# Bran_Download.net
KiCad netlist of a schematic drawn in Altium Designer
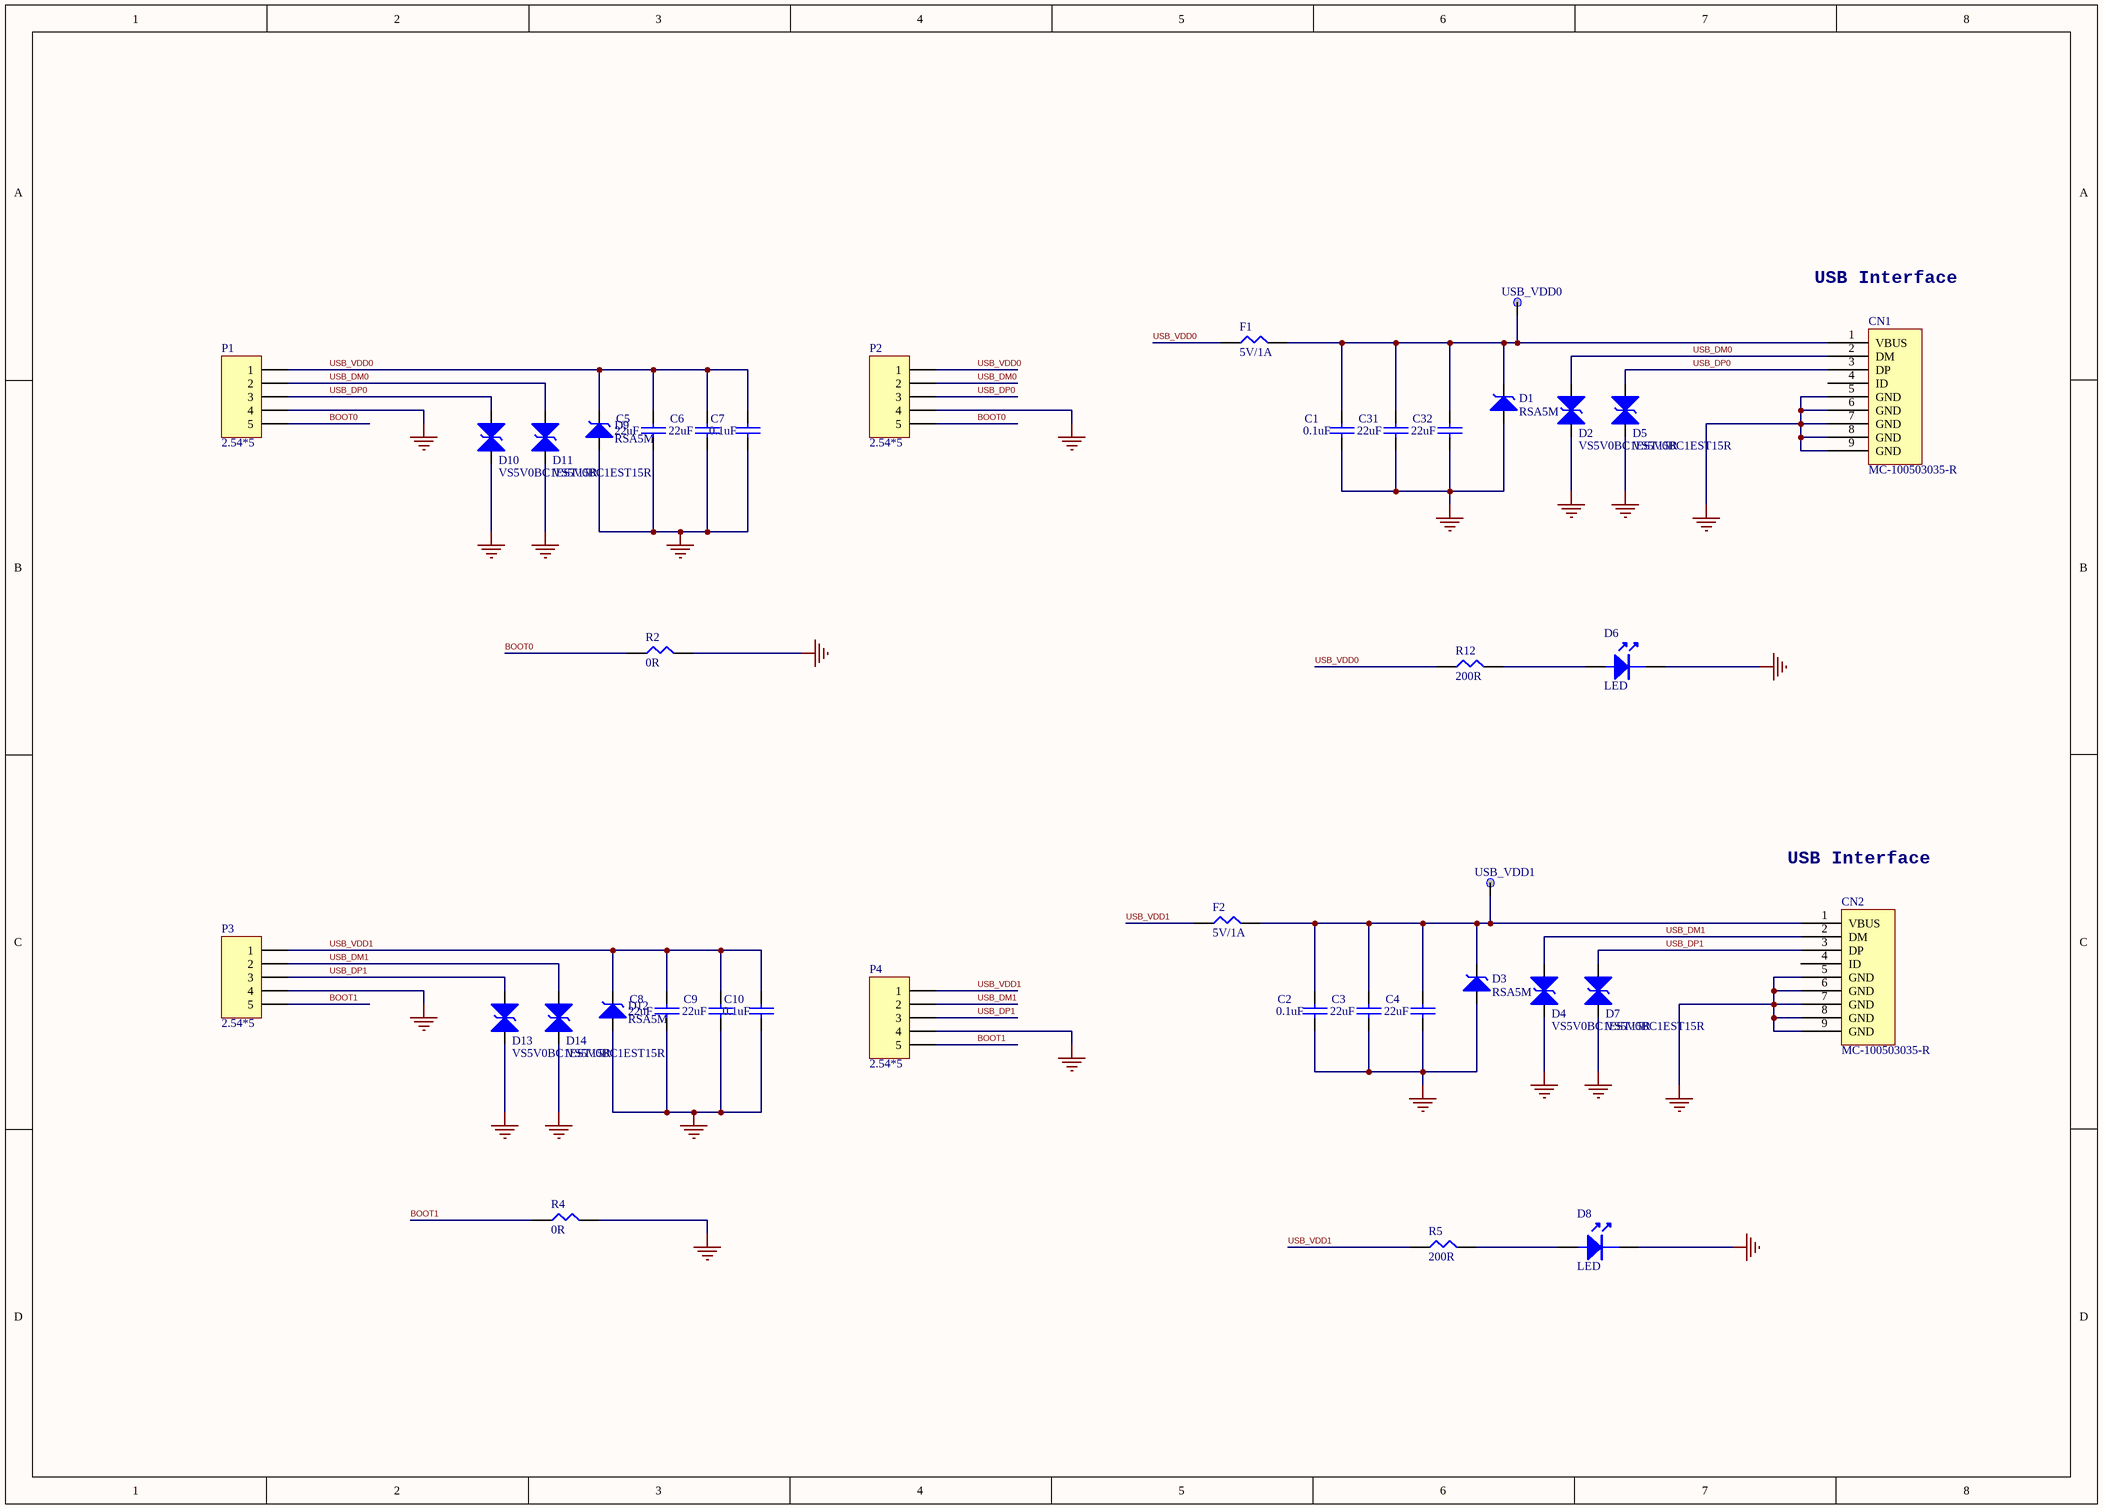
[diagram p0: Bran_Download.SchDoc]

(export (version "E")
  (design (tool "Eeschema 10.0.6"))
  (components
    (comp (ref "C1")
      (value "0.1uF")
      (footprint "0603C")
      (description "厂家：Murata，型号：GRM188R61A106KE69D")
      (libsource (lib "*") (part "CAP"))
    )
    (comp (ref "C2")
      (value "0.1uF")
      (footprint "0603C")
      (description "厂家：Murata，型号：GRM188R61A106KE69D")
      (libsource (lib "*") (part "CAP"))
    )
    (comp (ref "C3")
      (value "22uF")
      (footprint "0603C")
      (description "厂家：Murata，型号：GRM188R61A106KE69D")
      (libsource (lib "*") (part "CAP"))
    )
    (comp (ref "C4")
      (value "22uF")
      (footprint "0603C")
      (description "厂家：Murata，型号：GRM188R61A106KE69D")
      (libsource (lib "*") (part "CAP"))
    )
    (comp (ref "C5")
      (value "22uF")
      (footprint "0603C")
      (description "厂家：Murata，型号：GRM188R61A106KE69D")
      (libsource (lib "*") (part "CAP"))
    )
    (comp (ref "C6")
      (value "22uF")
      (footprint "0603C")
      (description "厂家：Murata，型号：GRM188R61A106KE69D")
      (libsource (lib "*") (part "CAP"))
    )
    (comp (ref "C7")
      (value "0.1uF")
      (footprint "0603C")
      (description "厂家：Murata，型号：GRM188R61A106KE69D")
      (libsource (lib "*") (part "CAP"))
    )
    (comp (ref "C8")
      (value "22uF")
      (footprint "0603C")
      (description "厂家：Murata，型号：GRM188R61A106KE69D")
      (libsource (lib "*") (part "CAP"))
    )
    (comp (ref "C9")
      (value "22uF")
      (footprint "0603C")
      (description "厂家：Murata，型号：GRM188R61A106KE69D")
      (libsource (lib "*") (part "CAP"))
    )
    (comp (ref "C10")
      (value "0.1uF")
      (footprint "0603C")
      (description "厂家：Murata，型号：GRM188R61A106KE69D")
      (libsource (lib "*") (part "CAP"))
    )
    (comp (ref "C31")
      (value "22uF")
      (footprint "0603C")
      (description "厂家：Murata，型号：GRM188R61A106KE69D")
      (libsource (lib "*") (part "CAP"))
    )
    (comp (ref "C32")
      (value "22uF")
      (footprint "0603C")
      (description "厂家：Murata，型号：GRM188R61A106KE69D")
      (libsource (lib "*") (part "CAP"))
    )
    (comp (ref "CN1")
      (value "MC-100503035-R")
      (footprint "MICRO-USB-乐沪")
      (libsource (lib "mic_usb_assy FPC") (part "475900001"))
    )
    (comp (ref "CN2")
      (value "MC-100503035-R")
      (footprint "MICRO-USB-乐沪")
      (libsource (lib "mic_usb_assy FPC") (part "475900001"))
    )
    (comp (ref "D1")
      (value "RSA5M")
      (footprint "PMDU")
      (description "厂家：ROHM，型号：VMNZC6.8CST2RA")
      (libsource (lib "CCS801 VOC") (part "ESD_1"))
    )
    (comp (ref "D2")
      (value "VS5V0BC1EST15R")
      (footprint "ESD_0402")
      (description "厂家：ROHM，型号：VMNZC6.8CST2RA")
      (libsource (lib "Amber") (part "ESD_1"))
    )
    (comp (ref "D3")
      (value "RSA5M")
      (footprint "PMDU")
      (description "厂家：ROHM，型号：VMNZC6.8CST2RA")
      (libsource (lib "CCS801 VOC") (part "ESD_1"))
    )
    (comp (ref "D4")
      (value "VS5V0BC1EST15R")
      (footprint "ESD_0402")
      (description "厂家：ROHM，型号：VMNZC6.8CST2RA")
      (libsource (lib "Amber") (part "ESD_1"))
    )
    (comp (ref "D5")
      (value "VS5V0BC1EST15R")
      (footprint "ESD_0402")
      (description "厂家：ROHM，型号：VMNZC6.8CST2RA")
      (libsource (lib "Amber") (part "ESD_1"))
    )
    (comp (ref "D6")
      (value "LED")
      (footprint "0402LED")
      (description "厂家：ROHM，型号：SCMP13WBC8W1**")
      (libsource (lib "Schlib1") (part "LED"))
    )
    (comp (ref "D7")
      (value "VS5V0BC1EST15R")
      (footprint "ESD_0402")
      (description "厂家：ROHM，型号：VMNZC6.8CST2RA")
      (libsource (lib "Amber") (part "ESD_1"))
    )
    (comp (ref "D8")
      (value "LED")
      (footprint "0402LED")
      (description "厂家：ROHM，型号：SCMP13WBC8W1**")
      (libsource (lib "Schlib1") (part "LED"))
    )
    (comp (ref "D9")
      (value "RSA5M")
      (footprint "PMDU")
      (description "厂家：ROHM，型号：VMNZC6.8CST2RA")
      (libsource (lib "CCS801 VOC") (part "ESD_1"))
    )
    (comp (ref "D10")
      (value "VS5V0BC1EST15R")
      (footprint "ESD_0402")
      (description "厂家：ROHM，型号：VMNZC6.8CST2RA")
      (libsource (lib "Amber") (part "ESD_1"))
    )
    (comp (ref "D11")
      (value "VS5V0BC1EST15R")
      (footprint "ESD_0402")
      (description "厂家：ROHM，型号：VMNZC6.8CST2RA")
      (libsource (lib "Amber") (part "ESD_1"))
    )
    (comp (ref "D12")
      (value "RSA5M")
      (footprint "PMDU")
      (description "厂家：ROHM，型号：VMNZC6.8CST2RA")
      (libsource (lib "CCS801 VOC") (part "ESD_1"))
    )
    (comp (ref "D13")
      (value "VS5V0BC1EST15R")
      (footprint "ESD_0402")
      (description "厂家：ROHM，型号：VMNZC6.8CST2RA")
      (libsource (lib "Amber") (part "ESD_1"))
    )
    (comp (ref "D14")
      (value "VS5V0BC1EST15R")
      (footprint "ESD_0402")
      (description "厂家：ROHM，型号：VMNZC6.8CST2RA")
      (libsource (lib "Amber") (part "ESD_1"))
    )
    (comp (ref "F1")
      (value "5V/1A")
      (footprint "0603R")
      (description "厂家：Yageo，型号：RC0402FR-07100KL")
      (libsource (lib "Schlib1") (part "RES"))
    )
    (comp (ref "F2")
      (value "5V/1A")
      (footprint "0603R")
      (description "厂家：Yageo，型号：RC0402FR-07100KL")
      (libsource (lib "Schlib1") (part "RES"))
    )
    (comp (ref "P1")
      (value "2.54*5")
      (footprint "HDR1X5")
      (description "Header, 5-Pin")
      (fields (field (name "PUBLISHER") "Altium Limited"))
      (libsource (lib "Miscellaneous Connectors") (part "Header 5"))
    )
    (comp (ref "P2")
      (value "2.54*5")
      (footprint "HDR1X5")
      (description "Header, 5-Pin")
      (fields (field (name "PUBLISHER") "Altium Limited"))
      (libsource (lib "Miscellaneous Connectors") (part "Header 5"))
    )
    (comp (ref "P3")
      (value "2.54*5")
      (footprint "HDR1X5")
      (description "Header, 5-Pin")
      (fields (field (name "PUBLISHER") "Altium Limited"))
      (libsource (lib "Miscellaneous Connectors") (part "Header 5"))
    )
    (comp (ref "P4")
      (value "2.54*5")
      (footprint "HDR1X5")
      (description "Header, 5-Pin")
      (fields (field (name "PUBLISHER") "Altium Limited"))
      (libsource (lib "Miscellaneous Connectors") (part "Header 5"))
    )
    (comp (ref "R2")
      (value "0R")
      (footprint "0603R")
      (description "厂家：Yageo，型号：RC0402FR-07100KL")
      (libsource (lib "Schlib1") (part "RES"))
    )
    (comp (ref "R4")
      (value "0R")
      (footprint "0603R")
      (description "厂家：Yageo，型号：RC0402FR-07100KL")
      (libsource (lib "Schlib1") (part "RES"))
    )
    (comp (ref "R5")
      (value "200R")
      (footprint "0603R")
      (description "厂家：Yageo，型号：RC0402FR-07100KL")
      (libsource (lib "Schlib1") (part "RES"))
    )
    (comp (ref "R12")
      (value "200R")
      (footprint "0603R")
      (description "厂家：Yageo，型号：RC0402FR-07100KL")
      (libsource (lib "Schlib1") (part "RES"))
    )
    (comp (ref "USB_VDD0") (value "TP") (footprint "TP_C40") (libsource (lib "Almos") (part "TP")))
    (comp (ref "USB_VDD1") (value "TP") (footprint "TP_C40") (libsource (lib "Almos") (part "TP")))
  )
  (nets
    (net (code "1") (name "/BOOT0") (class "Default")
      (node (ref "P1") (pin "5") (pinfunction "5_5") (pintype "passive"))
      (node (ref "P2") (pin "5") (pinfunction "5_5") (pintype "passive"))
      (node (ref "R2") (pin "1") (pinfunction "1_1") (pintype "passive"))
    )
    (net (code "2") (name "/BOOT1") (class "Default")
      (node (ref "P3") (pin "5") (pinfunction "5_5") (pintype "passive"))
      (node (ref "P4") (pin "5") (pinfunction "5_5") (pintype "passive"))
      (node (ref "R4") (pin "1") (pinfunction "1_1") (pintype "passive"))
    )
    (net (code "3") (name "/USB_DM0") (class "Default")
      (node (ref "CN1") (pin "2") (pinfunction "DM_2") (pintype "passive"))
      (node (ref "D11") (pin "2") (pinfunction "dIode2_2") (pintype "passive"))
      (node (ref "D2") (pin "2") (pinfunction "dIode2_2") (pintype "passive"))
      (node (ref "P1") (pin "2") (pinfunction "2_2") (pintype "passive"))
      (node (ref "P2") (pin "2") (pinfunction "2_2") (pintype "passive"))
    )
    (net (code "4") (name "/USB_DM1") (class "Default")
      (node (ref "CN2") (pin "2") (pinfunction "DM_2") (pintype "passive"))
      (node (ref "D14") (pin "2") (pinfunction "dIode2_2") (pintype "passive"))
      (node (ref "D4") (pin "2") (pinfunction "dIode2_2") (pintype "passive"))
      (node (ref "P3") (pin "2") (pinfunction "2_2") (pintype "passive"))
      (node (ref "P4") (pin "2") (pinfunction "2_2") (pintype "passive"))
    )
    (net (code "5") (name "/USB_DP0") (class "Default")
      (node (ref "CN1") (pin "3") (pinfunction "DP_3") (pintype "passive"))
      (node (ref "D10") (pin "2") (pinfunction "dIode2_2") (pintype "passive"))
      (node (ref "D5") (pin "2") (pinfunction "dIode2_2") (pintype "passive"))
      (node (ref "P1") (pin "3") (pinfunction "3_3") (pintype "passive"))
      (node (ref "P2") (pin "3") (pinfunction "3_3") (pintype "passive"))
    )
    (net (code "6") (name "/USB_DP1") (class "Default")
      (node (ref "CN2") (pin "3") (pinfunction "DP_3") (pintype "passive"))
      (node (ref "D13") (pin "2") (pinfunction "dIode2_2") (pintype "passive"))
      (node (ref "D7") (pin "2") (pinfunction "dIode2_2") (pintype "passive"))
      (node (ref "P3") (pin "3") (pinfunction "3_3") (pintype "passive"))
      (node (ref "P4") (pin "3") (pinfunction "3_3") (pintype "passive"))
    )
    (net (code "7") (name "/USB_VDD0") (class "Default")
      (node (ref "C5") (pin "1") (pinfunction "1_1") (pintype "passive"))
      (node (ref "C6") (pin "1") (pinfunction "1_1") (pintype "passive"))
      (node (ref "C7") (pin "1") (pinfunction "1_1") (pintype "passive"))
      (node (ref "D9") (pin "1") (pinfunction "Diode1_1") (pintype "passive"))
      (node (ref "F1") (pin "1") (pinfunction "1_1") (pintype "passive"))
      (node (ref "P1") (pin "1") (pinfunction "1_1") (pintype "passive"))
      (node (ref "P2") (pin "1") (pinfunction "1_1") (pintype "passive"))
      (node (ref "R12") (pin "1") (pinfunction "1_1") (pintype "passive"))
    )
    (net (code "8") (name "/USB_VDD1") (class "Default")
      (node (ref "C10") (pin "1") (pinfunction "1_1") (pintype "passive"))
      (node (ref "C8") (pin "1") (pinfunction "1_1") (pintype "passive"))
      (node (ref "C9") (pin "1") (pinfunction "1_1") (pintype "passive"))
      (node (ref "D12") (pin "1") (pinfunction "Diode1_1") (pintype "passive"))
      (node (ref "F2") (pin "1") (pinfunction "1_1") (pintype "passive"))
      (node (ref "P3") (pin "1") (pinfunction "1_1") (pintype "passive"))
      (node (ref "P4") (pin "1") (pinfunction "1_1") (pintype "passive"))
      (node (ref "R5") (pin "1") (pinfunction "1_1") (pintype "passive"))
    )
    (net (code "9") (name "GND") (class "Default")
      (node (ref "C1") (pin "2") (pinfunction "2_2") (pintype "passive"))
      (node (ref "C10") (pin "2") (pinfunction "2_2") (pintype "passive"))
      (node (ref "C2") (pin "2") (pinfunction "2_2") (pintype "passive"))
      (node (ref "C3") (pin "2") (pinfunction "2_2") (pintype "passive"))
      (node (ref "C31") (pin "2") (pinfunction "2_2") (pintype "passive"))
      (node (ref "C32") (pin "2") (pinfunction "2_2") (pintype "passive"))
      (node (ref "C4") (pin "2") (pinfunction "2_2") (pintype "passive"))
      (node (ref "C5") (pin "2") (pinfunction "2_2") (pintype "passive"))
      (node (ref "C6") (pin "2") (pinfunction "2_2") (pintype "passive"))
      (node (ref "C7") (pin "2") (pinfunction "2_2") (pintype "passive"))
      (node (ref "C8") (pin "2") (pinfunction "2_2") (pintype "passive"))
      (node (ref "C9") (pin "2") (pinfunction "2_2") (pintype "passive"))
      (node (ref "CN1") (pin "5") (pinfunction "GND_5") (pintype "passive"))
      (node (ref "CN1") (pin "6") (pinfunction "GND_6") (pintype "passive"))
      (node (ref "CN1") (pin "7") (pinfunction "GND_7") (pintype "passive"))
      (node (ref "CN1") (pin "8") (pinfunction "GND_8") (pintype "passive"))
      (node (ref "CN1") (pin "9") (pinfunction "GND_9") (pintype "passive"))
      (node (ref "CN2") (pin "5") (pinfunction "GND_5") (pintype "passive"))
      (node (ref "CN2") (pin "6") (pinfunction "GND_6") (pintype "passive"))
      (node (ref "CN2") (pin "7") (pinfunction "GND_7") (pintype "passive"))
      (node (ref "CN2") (pin "8") (pinfunction "GND_8") (pintype "passive"))
      (node (ref "CN2") (pin "9") (pinfunction "GND_9") (pintype "passive"))
      (node (ref "D1") (pin "2") (pinfunction "dIode2_2") (pintype "passive"))
      (node (ref "D10") (pin "1") (pinfunction "Diode1_1") (pintype "passive"))
      (node (ref "D11") (pin "1") (pinfunction "Diode1_1") (pintype "passive"))
      (node (ref "D12") (pin "2") (pinfunction "dIode2_2") (pintype "passive"))
      (node (ref "D13") (pin "1") (pinfunction "Diode1_1") (pintype "passive"))
      (node (ref "D14") (pin "1") (pinfunction "Diode1_1") (pintype "passive"))
      (node (ref "D2") (pin "1") (pinfunction "Diode1_1") (pintype "passive"))
      (node (ref "D3") (pin "2") (pinfunction "dIode2_2") (pintype "passive"))
      (node (ref "D4") (pin "1") (pinfunction "Diode1_1") (pintype "passive"))
      (node (ref "D5") (pin "1") (pinfunction "Diode1_1") (pintype "passive"))
      (node (ref "D6") (pin "1") (pinfunction "1_1") (pintype "passive"))
      (node (ref "D7") (pin "1") (pinfunction "Diode1_1") (pintype "passive"))
      (node (ref "D8") (pin "1") (pinfunction "1_1") (pintype "passive"))
      (node (ref "D9") (pin "2") (pinfunction "dIode2_2") (pintype "passive"))
      (node (ref "P1") (pin "4") (pinfunction "4_4") (pintype "passive"))
      (node (ref "P2") (pin "4") (pinfunction "4_4") (pintype "passive"))
      (node (ref "P3") (pin "4") (pinfunction "4_4") (pintype "passive"))
      (node (ref "P4") (pin "4") (pinfunction "4_4") (pintype "passive"))
      (node (ref "R2") (pin "2") (pinfunction "2_2") (pintype "passive"))
      (node (ref "R4") (pin "2") (pinfunction "2_2") (pintype "passive"))
    )
    (net (code "10") (name "Net-(CN1-VBUS)") (class "Default")
      (node (ref "C1") (pin "1") (pinfunction "1_1") (pintype "passive"))
      (node (ref "C31") (pin "1") (pinfunction "1_1") (pintype "passive"))
      (node (ref "C32") (pin "1") (pinfunction "1_1") (pintype "passive"))
      (node (ref "CN1") (pin "1") (pinfunction "VBUS_1") (pintype "passive"))
      (node (ref "D1") (pin "1") (pinfunction "Diode1_1") (pintype "passive"))
      (node (ref "F1") (pin "2") (pinfunction "2_2") (pintype "passive"))
      (node (ref "USB_VDD0") (pin "1") (pinfunction "1_1") (pintype "passive"))
    )
    (net (code "11") (name "Net-(CN2-VBUS)") (class "Default")
      (node (ref "C2") (pin "1") (pinfunction "1_1") (pintype "passive"))
      (node (ref "C3") (pin "1") (pinfunction "1_1") (pintype "passive"))
      (node (ref "C4") (pin "1") (pinfunction "1_1") (pintype "passive"))
      (node (ref "CN2") (pin "1") (pinfunction "VBUS_1") (pintype "passive"))
      (node (ref "D3") (pin "1") (pinfunction "Diode1_1") (pintype "passive"))
      (node (ref "F2") (pin "2") (pinfunction "2_2") (pintype "passive"))
      (node (ref "USB_VDD1") (pin "1") (pinfunction "1_1") (pintype "passive"))
    )
    (net (code "12") (name "Net-(D6-Pad2)") (class "Default")
      (node (ref "D6") (pin "2") (pinfunction "2_2") (pintype "passive"))
      (node (ref "R12") (pin "2") (pinfunction "2_2") (pintype "passive"))
    )
    (net (code "13") (name "Net-(D8-Pad2)") (class "Default")
      (node (ref "D8") (pin "2") (pinfunction "2_2") (pintype "passive"))
      (node (ref "R5") (pin "2") (pinfunction "2_2") (pintype "passive"))
    )
    (net (code "14") (name "unconnected-(CN1-ID-Pad4)") (class "Default")
      (node (ref "CN1") (pin "4") (pinfunction "ID_4") (pintype "passive"))
    )
    (net (code "15") (name "unconnected-(CN2-ID-Pad4)") (class "Default")
      (node (ref "CN2") (pin "4") (pinfunction "ID_4") (pintype "passive"))
    )
  )
)
